# pic32.net
KiCad netlist of a schematic drawn in EAGLE
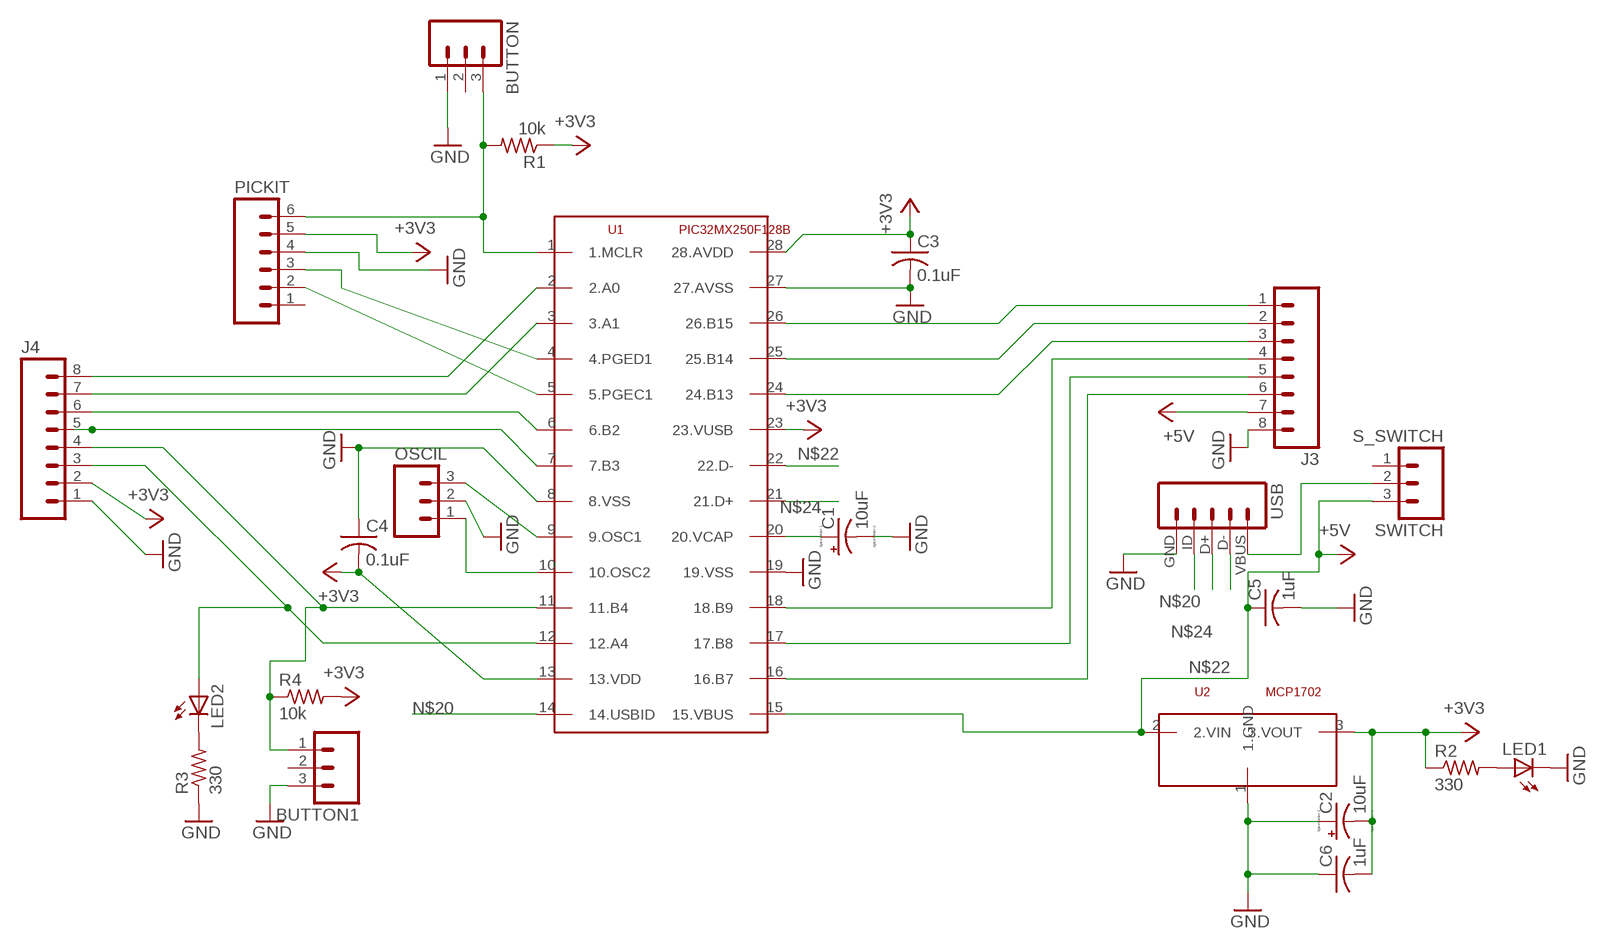
[diagram p0: schematic, sheet 1]

(export (version "E")
  (design (tool "Eeschema 10.0.6"))
  (components
    (comp (ref "BUTTON")
      (value "M03PTH")
      (footprint "eagle-import:1X03")
      (libsource (lib "eagle-import") (part "M03PTH"))
    )
    (comp (ref "BUTTON1")
      (value "M03PTH")
      (footprint "eagle-import:1X03")
      (libsource (lib "eagle-import") (part "M03PTH"))
    )
    (comp (ref "C1")
      (value "10uF")
      (footprint "eagle-import:TT2D4")
      (libsource (lib "eagle-import") (part "CPOL-USTT2D4"))
    )
    (comp (ref "C2")
      (value "10uF")
      (footprint "eagle-import:TT2D4")
      (libsource (lib "eagle-import") (part "CPOL-USTT2D4"))
    )
    (comp (ref "C3")
      (value "0.1uF")
      (footprint "eagle-import:C025-024X044")
      (libsource (lib "eagle-import") (part "C-US025-024X044"))
    )
    (comp (ref "C4")
      (value "0.1uF")
      (footprint "eagle-import:C025-024X044")
      (libsource (lib "eagle-import") (part "C-US025-024X044"))
    )
    (comp (ref "C5")
      (value "1uF")
      (footprint "eagle-import:C025-024X044")
      (libsource (lib "eagle-import") (part "C-US025-024X044"))
    )
    (comp (ref "C6")
      (value "1uF")
      (footprint "eagle-import:C025-024X044")
      (libsource (lib "eagle-import") (part "C-US025-024X044"))
    )
    (comp (ref "J3")
      (value "M08")
      (footprint "eagle-import:1X08_ROUND")
      (libsource (lib "eagle-import") (part "M08"))
    )
    (comp (ref "J4")
      (value "M08")
      (footprint "eagle-import:1X08_ROUND")
      (libsource (lib "eagle-import") (part "M08"))
    )
    (comp (ref "LED1")
      (value "LED3MM")
      (footprint "eagle-import:LED3MM")
      (libsource (lib "eagle-import") (part "led_LED3MM"))
    )
    (comp (ref "LED2")
      (value "LED3MM")
      (footprint "eagle-import:LED3MM")
      (libsource (lib "eagle-import") (part "LED3MM"))
    )
    (comp (ref "OSCIL")
      (value "M03PTH")
      (footprint "eagle-import:1X03")
      (libsource (lib "eagle-import") (part "M03PTH"))
    )
    (comp (ref "PICKIT")
      (value "M06SILK_FEMALE_PTH")
      (footprint "eagle-import:1X06")
      (libsource (lib "eagle-import") (part "M06SILK_FEMALE_PTH"))
    )
    (comp (ref "R1")
      (value "10k")
      (footprint "eagle-import:0207_7")
      (libsource (lib "eagle-import") (part "resistor_R-US_0207/7"))
    )
    (comp (ref "R2")
      (value "330")
      (footprint "eagle-import:0207_7")
      (libsource (lib "eagle-import") (part "R-US_0207/7"))
    )
    (comp (ref "R3")
      (value "330")
      (footprint "eagle-import:0207_7")
      (libsource (lib "eagle-import") (part "R-US_0207/7"))
    )
    (comp (ref "R4")
      (value "10k")
      (footprint "eagle-import:0207_7")
      (libsource (lib "eagle-import") (part "R-US_0207/7"))
    )
    (comp (ref "SWITCH")
      (value "S_SWITCH")
      (footprint "eagle-import:S_SWITCH")
      (libsource (lib "eagle-import") (part "S_SWITCH"))
    )
    (comp (ref "U1")
      (value "PIC32MX250F128B")
      (footprint "eagle-import:DIL28-3")
      (libsource (lib "eagle-import") (part "PIC32"))
    )
    (comp (ref "U2")
      (value "MCP1702")
      (footprint "eagle-import:TO92")
      (libsource (lib "eagle-import") (part "MCP1702"))
    )
    (comp (ref "USB")
      (value "M05")
      (footprint "eagle-import:USB-MB-H")
      (libsource (lib "eagle-import") (part "M05"))
    )
  )
  (nets
    (net (code "1") (name "+3V3") (class "Default")
      (node (ref "C2") (pin "-") (pinfunction "-_-") (pintype "passive"))
      (node (ref "C3") (pin "1") (pinfunction "1_1") (pintype "passive"))
      (node (ref "C4") (pin "2") (pinfunction "2_2") (pintype "passive"))
      (node (ref "C6") (pin "2") (pinfunction "2_2") (pintype "passive"))
      (node (ref "J4") (pin "2") (pinfunction "2_2") (pintype "passive"))
      (node (ref "PICKIT") (pin "5") (pinfunction "5_5") (pintype "passive"))
      (node (ref "R1") (pin "1") (pinfunction "1_1") (pintype "passive"))
      (node (ref "R2") (pin "1") (pinfunction "1_1") (pintype "passive"))
      (node (ref "R4") (pin "2") (pinfunction "2_2") (pintype "passive"))
      (node (ref "U1") (pin "13") (pinfunction "13.VDD_13") (pintype "bidirectional"))
      (node (ref "U1") (pin "23") (pinfunction "23.VUSB_23") (pintype "bidirectional"))
      (node (ref "U1") (pin "28") (pinfunction "28.AVDD_28") (pintype "bidirectional"))
      (node (ref "U2") (pin "3") (pinfunction "3.VOUT_3") (pintype "bidirectional"))
    )
    (net (code "2") (name "+5V") (class "Default")
      (node (ref "C5") (pin "1") (pinfunction "1_1") (pintype "passive"))
      (node (ref "J3") (pin "7") (pinfunction "7_7") (pintype "passive"))
      (node (ref "SWITCH") (pin "3") (pinfunction "3_3") (pintype "passive"))
      (node (ref "U1") (pin "15") (pinfunction "15.VBUS_15") (pintype "bidirectional"))
      (node (ref "U2") (pin "2") (pinfunction "2.VIN_2") (pintype "bidirectional"))
    )
    (net (code "3") (name "/N$20") (class "Default")
      (node (ref "U1") (pin "14") (pinfunction "14.USBID_14") (pintype "bidirectional"))
      (node (ref "USB") (pin "ID") (pinfunction "2_ID") (pintype "passive"))
    )
    (net (code "4") (name "/N$22") (class "Default")
      (node (ref "U1") (pin "22") (pinfunction "22.D-_22") (pintype "bidirectional"))
      (node (ref "USB") (pin "D-") (pinfunction "4_D-") (pintype "passive"))
    )
    (net (code "5") (name "/N$24") (class "Default")
      (node (ref "U1") (pin "21") (pinfunction "21.D+_21") (pintype "bidirectional"))
      (node (ref "USB") (pin "D+") (pinfunction "3_D+") (pintype "passive"))
    )
    (net (code "6") (name "GND") (class "Default")
      (node (ref "BUTTON") (pin "1") (pinfunction "1_1") (pintype "passive"))
      (node (ref "BUTTON1") (pin "3") (pinfunction "3_3") (pintype "passive"))
      (node (ref "C1") (pin "-") (pinfunction "-_-") (pintype "passive"))
      (node (ref "C2") (pin "+") (pinfunction "+_+") (pintype "passive"))
      (node (ref "C3") (pin "2") (pinfunction "2_2") (pintype "passive"))
      (node (ref "C4") (pin "1") (pinfunction "1_1") (pintype "passive"))
      (node (ref "C5") (pin "2") (pinfunction "2_2") (pintype "passive"))
      (node (ref "C6") (pin "1") (pinfunction "1_1") (pintype "passive"))
      (node (ref "J3") (pin "8") (pinfunction "8_8") (pintype "passive"))
      (node (ref "J4") (pin "1") (pinfunction "1_1") (pintype "passive"))
      (node (ref "LED1") (pin "K") (pinfunction "C_K") (pintype "passive"))
      (node (ref "OSCIL") (pin "2") (pinfunction "2_2") (pintype "passive"))
      (node (ref "PICKIT") (pin "4") (pinfunction "4_4") (pintype "passive"))
      (node (ref "R3") (pin "1") (pinfunction "1_1") (pintype "passive"))
      (node (ref "U1") (pin "19") (pinfunction "19.VSS_19") (pintype "bidirectional"))
      (node (ref "U1") (pin "27") (pinfunction "27.AVSS_27") (pintype "bidirectional"))
      (node (ref "U1") (pin "8") (pinfunction "8.VSS_8") (pintype "bidirectional"))
      (node (ref "U2") (pin "1") (pinfunction "1.GND_1") (pintype "bidirectional"))
      (node (ref "USB") (pin "GND") (pinfunction "1_GND") (pintype "passive"))
    )
    (net (code "7") (name "Net-(LED1-PadA)") (class "Default")
      (node (ref "LED1") (pin "A") (pinfunction "A_A") (pintype "passive"))
      (node (ref "R2") (pin "2") (pinfunction "2_2") (pintype "passive"))
    )
    (net (code "8") (name "Net-(LED2-C)") (class "Default")
      (node (ref "LED2") (pin "K") (pinfunction "C_K") (pintype "passive"))
      (node (ref "R3") (pin "2") (pinfunction "2_2") (pintype "passive"))
    )
    (net (code "9") (name "Net-(U1-1.MCLR)") (class "Default")
      (node (ref "BUTTON") (pin "3") (pinfunction "3_3") (pintype "passive"))
      (node (ref "PICKIT") (pin "6") (pinfunction "6_6") (pintype "passive"))
      (node (ref "R1") (pin "2") (pinfunction "2_2") (pintype "passive"))
      (node (ref "U1") (pin "1") (pinfunction "1.MCLR_1") (pintype "bidirectional"))
    )
    (net (code "10") (name "Net-(U1-2.A0)") (class "Default")
      (node (ref "J4") (pin "8") (pinfunction "8_8") (pintype "passive"))
      (node (ref "U1") (pin "2") (pinfunction "2.A0_2") (pintype "bidirectional"))
    )
    (net (code "11") (name "Net-(U1-3.A1)") (class "Default")
      (node (ref "J4") (pin "7") (pinfunction "7_7") (pintype "passive"))
      (node (ref "U1") (pin "3") (pinfunction "3.A1_3") (pintype "bidirectional"))
    )
    (net (code "12") (name "Net-(U1-4.PGED1)") (class "Default")
      (node (ref "PICKIT") (pin "3") (pinfunction "3_3") (pintype "passive"))
      (node (ref "U1") (pin "4") (pinfunction "4.PGED1_4") (pintype "bidirectional"))
    )
    (net (code "13") (name "Net-(U1-5.PGEC1)") (class "Default")
      (node (ref "PICKIT") (pin "2") (pinfunction "2_2") (pintype "passive"))
      (node (ref "U1") (pin "5") (pinfunction "5.PGEC1_5") (pintype "bidirectional"))
    )
    (net (code "14") (name "Net-(U1-6.B2)") (class "Default")
      (node (ref "J4") (pin "6") (pinfunction "6_6") (pintype "passive"))
      (node (ref "U1") (pin "6") (pinfunction "6.B2_6") (pintype "bidirectional"))
    )
    (net (code "15") (name "Net-(U1-7.B3)") (class "Default")
      (node (ref "J4") (pin "5") (pinfunction "5_5") (pintype "passive"))
      (node (ref "U1") (pin "7") (pinfunction "7.B3_7") (pintype "bidirectional"))
    )
    (net (code "16") (name "Net-(U1-9.OSC1)") (class "Default")
      (node (ref "OSCIL") (pin "3") (pinfunction "3_3") (pintype "passive"))
      (node (ref "U1") (pin "9") (pinfunction "9.OSC1_9") (pintype "bidirectional"))
    )
    (net (code "17") (name "Net-(U1-10.OSC2)") (class "Default")
      (node (ref "OSCIL") (pin "1") (pinfunction "1_1") (pintype "passive"))
      (node (ref "U1") (pin "10") (pinfunction "10.OSC2_10") (pintype "bidirectional"))
    )
    (net (code "18") (name "Net-(U1-11.B4)") (class "Default")
      (node (ref "BUTTON1") (pin "1") (pinfunction "1_1") (pintype "passive"))
      (node (ref "J4") (pin "4") (pinfunction "4_4") (pintype "passive"))
      (node (ref "R4") (pin "1") (pinfunction "1_1") (pintype "passive"))
      (node (ref "U1") (pin "11") (pinfunction "11.B4_11") (pintype "bidirectional"))
    )
    (net (code "19") (name "Net-(U1-12.A4)") (class "Default")
      (node (ref "J4") (pin "3") (pinfunction "3_3") (pintype "passive"))
      (node (ref "LED2") (pin "A") (pinfunction "A_A") (pintype "passive"))
      (node (ref "U1") (pin "12") (pinfunction "12.A4_12") (pintype "bidirectional"))
    )
    (net (code "20") (name "Net-(U1-16.B7)") (class "Default")
      (node (ref "J3") (pin "6") (pinfunction "6_6") (pintype "passive"))
      (node (ref "U1") (pin "16") (pinfunction "16.B7_16") (pintype "bidirectional"))
    )
    (net (code "21") (name "Net-(U1-17.B8)") (class "Default")
      (node (ref "J3") (pin "5") (pinfunction "5_5") (pintype "passive"))
      (node (ref "U1") (pin "17") (pinfunction "17.B8_17") (pintype "bidirectional"))
    )
    (net (code "22") (name "Net-(U1-18.B9)") (class "Default")
      (node (ref "J3") (pin "4") (pinfunction "4_4") (pintype "passive"))
      (node (ref "U1") (pin "18") (pinfunction "18.B9_18") (pintype "bidirectional"))
    )
    (net (code "23") (name "Net-(U1-20.VCAP)") (class "Default")
      (node (ref "C1") (pin "+") (pinfunction "+_+") (pintype "passive"))
      (node (ref "U1") (pin "20") (pinfunction "20.VCAP_20") (pintype "bidirectional"))
    )
    (net (code "24") (name "Net-(U1-24.B13)") (class "Default")
      (node (ref "J3") (pin "3") (pinfunction "3_3") (pintype "passive"))
      (node (ref "U1") (pin "24") (pinfunction "24.B13_24") (pintype "bidirectional"))
    )
    (net (code "25") (name "Net-(U1-25.B14)") (class "Default")
      (node (ref "J3") (pin "2") (pinfunction "2_2") (pintype "passive"))
      (node (ref "U1") (pin "25") (pinfunction "25.B14_25") (pintype "bidirectional"))
    )
    (net (code "26") (name "Net-(U1-26.B15)") (class "Default")
      (node (ref "J3") (pin "1") (pinfunction "1_1") (pintype "passive"))
      (node (ref "U1") (pin "26") (pinfunction "26.B15_26") (pintype "bidirectional"))
    )
    (net (code "27") (name "Net-(USB-5)") (class "Default")
      (node (ref "SWITCH") (pin "2") (pinfunction "2_2") (pintype "passive"))
      (node (ref "USB") (pin "VBUS") (pinfunction "5_VBUS") (pintype "passive"))
    )
    (net (code "28") (name "unconnected-(BUTTON-Pad2)") (class "Default")
      (node (ref "BUTTON") (pin "2") (pinfunction "2_2") (pintype "passive"))
    )
    (net (code "29") (name "unconnected-(BUTTON1-Pad2)") (class "Default")
      (node (ref "BUTTON1") (pin "2") (pinfunction "2_2") (pintype "passive"))
    )
    (net (code "30") (name "unconnected-(PICKIT-Pad1)") (class "Default")
      (node (ref "PICKIT") (pin "1") (pinfunction "1_1") (pintype "passive"))
    )
    (net (code "31") (name "unconnected-(SWITCH-Pad1)") (class "Default")
      (node (ref "SWITCH") (pin "1") (pinfunction "1_1") (pintype "passive"))
    )
  )
)
